# BPC_ProbeV1.net
KiCad netlist of a schematic drawn in Altium Designer
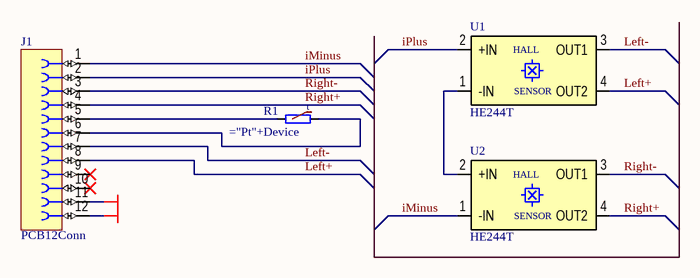
[diagram p0: BPC.ProbeV1.SchDoc]

(export (version "E")
  (design (tool "Eeschema 10.0.6"))
  (components
    (comp (ref "J1")
      (value "PCB12Conn")
      (footprint "PCB12Conn")
      (description "PCB Connector 12 pins")
      (libsource (lib "DDSintLib") (part "PCB12_Conn"))
    )
    (comp (ref "R1")
      (value "HRTS-5760-B-U-0-12")
      (footprint "HRTS-5760-B-U-0-12mini")
      (description "Pt1000 Temperature Sensors")
      (libsource (lib "DDSintLib") (part "HRTS-5760-B-U-0-12"))
    )
    (comp (ref "U1")
      (value "HE244T")
      (footprint "HE244T_LeftV1")
      (description "HE244 Series Analog Hall Sensor")
      (libsource (lib "DDSintLib") (part "HE244T"))
    )
    (comp (ref "U2")
      (value "HE244T")
      (footprint "HE244T_RightV1")
      (description "HE244 Series Analog Hall Sensor")
      (libsource (lib "DDSintLib") (part "HE244T"))
    )
  )
  (nets
    (net (code "1") (name "/Left+") (class "Default")
      (node (ref "J1") (pin "8") (pinfunction "8_8") (pintype "bidirectional"))
      (node (ref "U1") (pin "4") (pinfunction "OUT2_4") (pintype "bidirectional"))
    )
    (net (code "2") (name "/Left-") (class "Default")
      (node (ref "J1") (pin "7") (pinfunction "7_7") (pintype "bidirectional"))
      (node (ref "U1") (pin "3") (pinfunction "OUT1_3") (pintype "bidirectional"))
    )
    (net (code "3") (name "/Right+") (class "Default")
      (node (ref "J1") (pin "4") (pinfunction "4_4") (pintype "bidirectional"))
      (node (ref "U2") (pin "4") (pinfunction "OUT2_4") (pintype "bidirectional"))
    )
    (net (code "4") (name "/Right-") (class "Default")
      (node (ref "J1") (pin "3") (pinfunction "3_3") (pintype "bidirectional"))
      (node (ref "U2") (pin "3") (pinfunction "OUT1_3") (pintype "bidirectional"))
    )
    (net (code "5") (name "/iMinus") (class "Default")
      (node (ref "J1") (pin "1") (pinfunction "1_1") (pintype "bidirectional"))
      (node (ref "U2") (pin "1") (pinfunction "-IN_1") (pintype "bidirectional"))
    )
    (net (code "6") (name "/iPlus") (class "Default")
      (node (ref "J1") (pin "2") (pinfunction "2_2") (pintype "bidirectional"))
      (node (ref "U1") (pin "2") (pinfunction "+IN_2") (pintype "bidirectional"))
    )
    (net (code "7") (name "GND") (class "Default")
      (node (ref "J1") (pin "11") (pinfunction "11_11") (pintype "bidirectional"))
      (node (ref "J1") (pin "12") (pinfunction "12_12") (pintype "bidirectional"))
    )
    (net (code "8") (name "Net-(J1-Pad5)") (class "Default")
      (node (ref "J1") (pin "5") (pinfunction "5_5") (pintype "bidirectional"))
      (node (ref "R1") (pin "1") (pinfunction "1_1") (pintype "passive"))
    )
    (net (code "9") (name "Net-(J1-Pad6)") (class "Default")
      (node (ref "J1") (pin "6") (pinfunction "6_6") (pintype "bidirectional"))
      (node (ref "R1") (pin "2") (pinfunction "2_2") (pintype "passive"))
    )
    (net (code "10") (name "Net-(U1--IN)") (class "Default")
      (node (ref "U1") (pin "1") (pinfunction "-IN_1") (pintype "bidirectional"))
      (node (ref "U2") (pin "2") (pinfunction "+IN_2") (pintype "bidirectional"))
    )
    (net (code "11") (name "unconnected-(J1-Pad9)") (class "Default")
      (node (ref "J1") (pin "9") (pinfunction "9_9") (pintype "bidirectional+no_connect"))
    )
    (net (code "12") (name "unconnected-(J1-Pad10)") (class "Default")
      (node (ref "J1") (pin "10") (pinfunction "10_10") (pintype "bidirectional+no_connect"))
    )
  )
)
